# Sheet3.net
KiCad netlist of a schematic drawn in Altium Designer
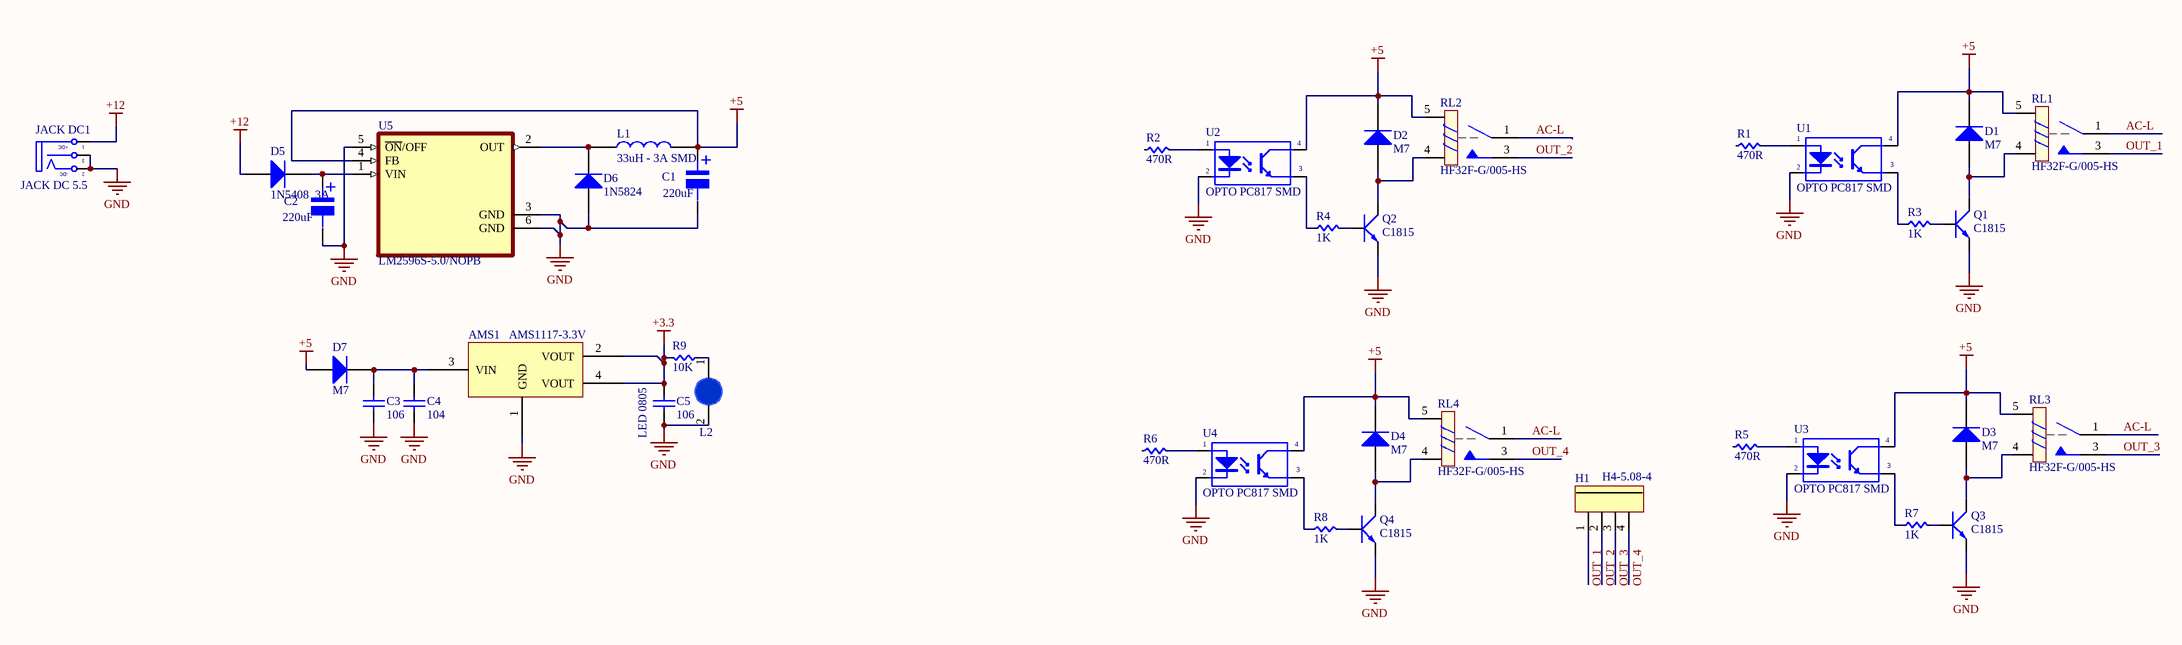
[diagram p0: Sheet3.SchDoc]

(export (version "E")
  (design (tool "Eeschema 10.0.6"))
  (components
    (comp (ref "AMS1")
      (value "AMS1117-3.3V")
      (footprint "SOT223")
      (description "Dán")
      (libsource (lib "Altium_Lib_by_KhueNguyenCreator") (part "AMS1117 SMD"))
    )
    (comp (ref "C1")
      (value "220uF")
      (footprint "tu nhom 10 (G)")
      (description "Dán")
      (libsource (lib "Altium_Lib_by_KhueNguyenCreator") (part "Tu Nhom 470uF 35V"))
    )
    (comp (ref "C2")
      (value "220uF")
      (footprint "tu nhom 10 (G)")
      (description "Dán")
      (libsource (lib "Altium_Lib_by_KhueNguyenCreator") (part "Tu Nhom 470uF 35V"))
    )
    (comp (ref "C3")
      (value "106")
      (footprint "tu 0805")
      (description "Dán")
      (libsource (lib "Altium_Lib_by_KhueNguyenCreator") (part "Tu 0805 106 16V 10%"))
    )
    (comp (ref "C4")
      (value "104")
      (footprint "tu 0805")
      (description "Dán")
      (libsource (lib "Altium_Lib_by_KhueNguyenCreator") (part "Tu 0805 104 50V 10%"))
    )
    (comp (ref "C5")
      (value "106")
      (footprint "tu 0805")
      (description "Dán")
      (libsource (lib "Altium_Lib_by_KhueNguyenCreator") (part "Tu 0805 106 16V 10%"))
    )
    (comp (ref "D1")
      (value "M7")
      (footprint "DIODE SMA")
      (description "Dán")
      (libsource (lib "Altium_Lib_by_KhueNguyenCreator") (part "Diode M7 ( 4007 )"))
    )
    (comp (ref "D2")
      (value "M7")
      (footprint "DIODE SMA")
      (description "Dán")
      (libsource (lib "Altium_Lib_by_KhueNguyenCreator") (part "Diode M7 ( 4007 )"))
    )
    (comp (ref "D3")
      (value "M7")
      (footprint "DIODE SMA")
      (description "Dán")
      (libsource (lib "Altium_Lib_by_KhueNguyenCreator") (part "Diode M7 ( 4007 )"))
    )
    (comp (ref "D4")
      (value "M7")
      (footprint "DIODE SMA")
      (description "Dán")
      (libsource (lib "Altium_Lib_by_KhueNguyenCreator") (part "Diode M7 ( 4007 )"))
    )
    (comp (ref "D5")
      (value "1N5408  3A")
      (footprint "DIODE SMA")
      (description "Dán")
      (libsource (lib "Altium_Lib_by_KhueNguyenCreator") (part "Diode M7 ( 4007 )"))
    )
    (comp (ref "D6")
      (value "1N5824")
      (footprint "DIODE SMA")
      (description "Dán")
      (libsource (lib "Altium_Lib_by_KhueNguyenCreator") (part "Diode SS34 ( 1N5822 )"))
    )
    (comp (ref "D7")
      (value "M7")
      (footprint "DIODE SMA")
      (description "Dán")
      (libsource (lib "Altium_Lib_by_KhueNguyenCreator") (part "Diode M7 ( 4007 )"))
    )
    (comp (ref "H1")
      (value "H4-5.08-4")
      (footprint "KF-5.08-4")
      (libsource (lib "iuh-thuc-hanh") (part "KF-5.08-4-R Cong"))
    )
    (comp (ref "JACK DC1")
      (value "JACK DC 5.5")
      (footprint "JACK DC 5.5")
      (libsource (lib "Altium_Lib_by_KhueNguyenCreator") (part "JACK DC 5.5"))
    )
    (comp (ref "L1")
      (value "33uH - 3A SMD")
      (footprint "Cuon Cam 12x12x10")
      (description "Dán")
      (libsource (lib "Altium_Lib_by_KhueNguyenCreator") (part "CUON CAM 100uH SMD"))
    )
    (comp (ref "L2")
      (value "LED 0805")
      (footprint "LED-0805-Blue")
      (description "Dán")
      (libsource (lib "Altium_Lib_by_KhueNguyenCreator") (part "LED 0805 Xanh Duong"))
    )
    (comp (ref "Q1")
      (value "C1815")
      (footprint "QTO-92")
      (description "NPN 600mW, ECB")
      (libsource (lib "syhaunguyen") (part "C1815"))
    )
    (comp (ref "Q2")
      (value "C1815")
      (footprint "QTO-92")
      (description "NPN 600mW, ECB")
      (libsource (lib "syhaunguyen") (part "C1815"))
    )
    (comp (ref "Q3")
      (value "C1815")
      (footprint "QTO-92")
      (description "NPN 600mW, ECB")
      (libsource (lib "syhaunguyen") (part "C1815"))
    )
    (comp (ref "Q4")
      (value "C1815")
      (footprint "QTO-92")
      (description "NPN 600mW, ECB")
      (libsource (lib "syhaunguyen") (part "C1815"))
    )
    (comp (ref "R1")
      (value "470R")
      (footprint "RES 0805")
      (description "RES SMD 0805")
      (fields
        (field (name "MANUFACTURER") "Vishay Dale")
        (field (name "MANUFACTURER PART NUMBER") "CRCW040210K0FKED")
      )
      (libsource (lib "Altium_Lib_by_KhueNguyenCreator") (part "RES 0805"))
    )
    (comp (ref "R2")
      (value "470R")
      (footprint "RES 0805")
      (description "RES SMD 0805")
      (fields
        (field (name "MANUFACTURER") "Vishay Dale")
        (field (name "MANUFACTURER PART NUMBER") "CRCW040210K0FKED")
      )
      (libsource (lib "Altium_Lib_by_KhueNguyenCreator") (part "RES 0805"))
    )
    (comp (ref "R3")
      (value "1K")
      (footprint "RES 0805")
      (description "RES SMD 0805")
      (fields
        (field (name "MANUFACTURER") "Vishay Dale")
        (field (name "MANUFACTURER PART NUMBER") "CRCW040210K0FKED")
      )
      (libsource (lib "Altium_Lib_by_KhueNguyenCreator") (part "RES 0805"))
    )
    (comp (ref "R4")
      (value "1K")
      (footprint "RES 0805")
      (description "RES SMD 0805")
      (fields
        (field (name "MANUFACTURER") "Vishay Dale")
        (field (name "MANUFACTURER PART NUMBER") "CRCW040210K0FKED")
      )
      (libsource (lib "Altium_Lib_by_KhueNguyenCreator") (part "RES 0805"))
    )
    (comp (ref "R5")
      (value "470R")
      (footprint "RES 0805")
      (description "RES SMD 0805")
      (fields
        (field (name "MANUFACTURER") "Vishay Dale")
        (field (name "MANUFACTURER PART NUMBER") "CRCW040210K0FKED")
      )
      (libsource (lib "Altium_Lib_by_KhueNguyenCreator") (part "RES 0805"))
    )
    (comp (ref "R6")
      (value "470R")
      (footprint "RES 0805")
      (description "RES SMD 0805")
      (fields
        (field (name "MANUFACTURER") "Vishay Dale")
        (field (name "MANUFACTURER PART NUMBER") "CRCW040210K0FKED")
      )
      (libsource (lib "Altium_Lib_by_KhueNguyenCreator") (part "RES 0805"))
    )
    (comp (ref "R7")
      (value "1K")
      (footprint "RES 0805")
      (description "RES SMD 0805")
      (fields
        (field (name "MANUFACTURER") "Vishay Dale")
        (field (name "MANUFACTURER PART NUMBER") "CRCW040210K0FKED")
      )
      (libsource (lib "Altium_Lib_by_KhueNguyenCreator") (part "RES 0805"))
    )
    (comp (ref "R8")
      (value "1K")
      (footprint "RES 0805")
      (description "RES SMD 0805")
      (fields
        (field (name "MANUFACTURER") "Vishay Dale")
        (field (name "MANUFACTURER PART NUMBER") "CRCW040210K0FKED")
      )
      (libsource (lib "Altium_Lib_by_KhueNguyenCreator") (part "RES 0805"))
    )
    (comp (ref "R9")
      (value "10K")
      (footprint "RES 0805")
      (description "RES SMD 0805")
      (fields
        (field (name "MANUFACTURER") "Vishay Dale")
        (field (name "MANUFACTURER PART NUMBER") "CRCW040210K0FKED")
      )
      (libsource (lib "Altium_Lib_by_KhueNguyenCreator") (part "RES 0805"))
    )
    (comp (ref "RL1")
      (value "HF32F-G/005-HS")
      (footprint "HF32F-G")
      (description "Relay hongfa 10A 4P HF32F-G/005-HS")
      (libsource (lib "iuh-thuc-hanh") (part "Relay HF 10A"))
    )
    (comp (ref "RL2")
      (value "HF32F-G/005-HS")
      (footprint "HF32F-G")
      (description "Relay hongfa 10A 4P HF32F-G/005-HS")
      (libsource (lib "iuh-thuc-hanh") (part "Relay HF 10A"))
    )
    (comp (ref "RL3")
      (value "HF32F-G/005-HS")
      (footprint "HF32F-G")
      (description "Relay hongfa 10A 4P HF32F-G/005-HS")
      (libsource (lib "iuh-thuc-hanh") (part "Relay HF 10A"))
    )
    (comp (ref "RL4")
      (value "HF32F-G/005-HS")
      (footprint "HF32F-G")
      (description "Relay hongfa 10A 4P HF32F-G/005-HS")
      (libsource (lib "iuh-thuc-hanh") (part "Relay HF 10A"))
    )
    (comp (ref "U1")
      (value "OPTO PC817 SMD")
      (footprint "SOP4")
      (description "Single Opto")
      (libsource (lib "Altium_Lib_by_KhueNguyenCreator") (part "OPTO PC817 SMD"))
    )
    (comp (ref "U2")
      (value "OPTO PC817 SMD")
      (footprint "SOP4")
      (description "Single Opto")
      (libsource (lib "Altium_Lib_by_KhueNguyenCreator") (part "OPTO PC817 SMD"))
    )
    (comp (ref "U3")
      (value "OPTO PC817 SMD")
      (footprint "SOP4")
      (description "Single Opto")
      (libsource (lib "Altium_Lib_by_KhueNguyenCreator") (part "OPTO PC817 SMD"))
    )
    (comp (ref "U4")
      (value "OPTO PC817 SMD")
      (footprint "SOP4")
      (description "Single Opto")
      (libsource (lib "Altium_Lib_by_KhueNguyenCreator") (part "OPTO PC817 SMD"))
    )
    (comp (ref "U5")
      (value "LM2596S-5.0/NOPB")
      (footprint "VREG_LM2596S-12/NOPB")
      (description "SIMPLE SWITCHERÂ® 4.5V to 40V, 3A Low Component Count Step-Down Regulator")
      (fields (field (name "MF") "Texas Instruments") (field (name "MP") "LM2596S-12/NOPB"))
      (libsource (lib "TuHap") (part "LM2596S-12/NOPB"))
    )
  )
  (nets
    (net (code "1") (name "+3.3") (class "Default")
      (node (ref "AMS1") (pin "2") (pinfunction "VOUT_2") (pintype "passive"))
      (node (ref "AMS1") (pin "4") (pinfunction "VOUT_4") (pintype "passive"))
      (node (ref "C5") (pin "1") (pinfunction "1_1") (pintype "passive"))
      (node (ref "R9") (pin "2") (pinfunction "2_2") (pintype "passive"))
    )
    (net (code "2") (name "+5") (class "Default")
      (node (ref "C1") (pin "1") (pinfunction "1_1") (pintype "passive"))
      (node (ref "D1") (pin "2") (pinfunction "K_2") (pintype "passive"))
      (node (ref "D2") (pin "2") (pinfunction "K_2") (pintype "passive"))
      (node (ref "D3") (pin "2") (pinfunction "K_2") (pintype "passive"))
      (node (ref "D4") (pin "2") (pinfunction "K_2") (pintype "passive"))
      (node (ref "D7") (pin "1") (pinfunction "A_1") (pintype "passive"))
      (node (ref "L1") (pin "2") (pinfunction "2_2") (pintype "passive"))
      (node (ref "RL1") (pin "5") (pinfunction "5_5") (pintype "passive"))
      (node (ref "RL2") (pin "5") (pinfunction "5_5") (pintype "passive"))
      (node (ref "RL3") (pin "5") (pinfunction "5_5") (pintype "passive"))
      (node (ref "RL4") (pin "5") (pinfunction "5_5") (pintype "passive"))
      (node (ref "U1") (pin "4") (pinfunction "C_4") (pintype "passive"))
      (node (ref "U2") (pin "4") (pinfunction "C_4") (pintype "passive"))
      (node (ref "U3") (pin "4") (pinfunction "C_4") (pintype "passive"))
      (node (ref "U4") (pin "4") (pinfunction "C_4") (pintype "passive"))
      (node (ref "U5") (pin "4") (pinfunction "FB_4") (pintype "input"))
    )
    (net (code "3") (name "+12") (class "Default")
      (node (ref "D5") (pin "1") (pinfunction "A_1") (pintype "passive"))
      (node (ref "JACK DC1") (pin "1") (pinfunction "T_1") (pintype "passive"))
    )
    (net (code "4") (name "/AC-L") (class "Default")
      (node (ref "RL1") (pin "1") (pinfunction "1_1") (pintype "passive"))
      (node (ref "RL2") (pin "1") (pinfunction "1_1") (pintype "passive"))
      (node (ref "RL3") (pin "1") (pinfunction "1_1") (pintype "passive"))
      (node (ref "RL4") (pin "1") (pinfunction "1_1") (pintype "passive"))
    )
    (net (code "5") (name "/OUT_1") (class "Default")
      (node (ref "H1") (pin "1") (pinfunction "1_1") (pintype "passive"))
      (node (ref "RL1") (pin "3") (pinfunction "3_3") (pintype "passive"))
    )
    (net (code "6") (name "/OUT_2") (class "Default")
      (node (ref "H1") (pin "2") (pinfunction "2_2") (pintype "passive"))
      (node (ref "RL2") (pin "3") (pinfunction "3_3") (pintype "passive"))
    )
    (net (code "7") (name "/OUT_3") (class "Default")
      (node (ref "H1") (pin "3") (pinfunction "3_3") (pintype "passive"))
      (node (ref "RL3") (pin "3") (pinfunction "3_3") (pintype "passive"))
    )
    (net (code "8") (name "/OUT_4") (class "Default")
      (node (ref "H1") (pin "4") (pinfunction "4_4") (pintype "passive"))
      (node (ref "RL4") (pin "3") (pinfunction "3_3") (pintype "passive"))
    )
    (net (code "9") (name "GND") (class "Default")
      (node (ref "AMS1") (pin "1") (pinfunction "GND_1") (pintype "passive"))
      (node (ref "C1") (pin "2") (pinfunction "2_2") (pintype "passive"))
      (node (ref "C2") (pin "2") (pinfunction "2_2") (pintype "passive"))
      (node (ref "C3") (pin "2") (pinfunction "2_2") (pintype "passive"))
      (node (ref "C4") (pin "2") (pinfunction "2_2") (pintype "passive"))
      (node (ref "C5") (pin "2") (pinfunction "2_2") (pintype "passive"))
      (node (ref "D6") (pin "1") (pinfunction "A_1") (pintype "passive"))
      (node (ref "JACK DC1") (pin "2") (pinfunction "TN_2") (pintype "passive"))
      (node (ref "JACK DC1") (pin "3") (pinfunction "S_3") (pintype "power_in"))
      (node (ref "L2") (pin "2") (pinfunction "K_2") (pintype "passive"))
      (node (ref "Q1") (pin "1") (pinfunction "E_1") (pintype "passive"))
      (node (ref "Q2") (pin "1") (pinfunction "E_1") (pintype "passive"))
      (node (ref "Q3") (pin "1") (pinfunction "E_1") (pintype "passive"))
      (node (ref "Q4") (pin "1") (pinfunction "E_1") (pintype "passive"))
      (node (ref "U1") (pin "2") (pinfunction "K_2") (pintype "passive"))
      (node (ref "U2") (pin "2") (pinfunction "K_2") (pintype "passive"))
      (node (ref "U3") (pin "2") (pinfunction "K_2") (pintype "passive"))
      (node (ref "U4") (pin "2") (pinfunction "K_2") (pintype "passive"))
      (node (ref "U5") (pin "3") (pinfunction "GND_3") (pintype "power_in"))
      (node (ref "U5") (pin "5") (pinfunction "~{ON}/OFF_5") (pintype "input"))
      (node (ref "U5") (pin "6") (pinfunction "GND_6") (pintype "power_in"))
    )
    (net (code "10") (name "Net-(AMS1-VIN)") (class "Default")
      (node (ref "AMS1") (pin "3") (pinfunction "VIN_3") (pintype "passive"))
      (node (ref "C3") (pin "1") (pinfunction "1_1") (pintype "passive"))
      (node (ref "C4") (pin "1") (pinfunction "1_1") (pintype "passive"))
      (node (ref "D7") (pin "2") (pinfunction "K_2") (pintype "passive"))
    )
    (net (code "11") (name "Net-(D1-A)") (class "Default")
      (node (ref "D1") (pin "1") (pinfunction "A_1") (pintype "passive"))
      (node (ref "Q1") (pin "2") (pinfunction "C_2") (pintype "passive"))
      (node (ref "RL1") (pin "4") (pinfunction "4_4") (pintype "passive"))
    )
    (net (code "12") (name "Net-(D2-A)") (class "Default")
      (node (ref "D2") (pin "1") (pinfunction "A_1") (pintype "passive"))
      (node (ref "Q2") (pin "2") (pinfunction "C_2") (pintype "passive"))
      (node (ref "RL2") (pin "4") (pinfunction "4_4") (pintype "passive"))
    )
    (net (code "13") (name "Net-(D3-A)") (class "Default")
      (node (ref "D3") (pin "1") (pinfunction "A_1") (pintype "passive"))
      (node (ref "Q3") (pin "2") (pinfunction "C_2") (pintype "passive"))
      (node (ref "RL3") (pin "4") (pinfunction "4_4") (pintype "passive"))
    )
    (net (code "14") (name "Net-(D4-A)") (class "Default")
      (node (ref "D4") (pin "1") (pinfunction "A_1") (pintype "passive"))
      (node (ref "Q4") (pin "2") (pinfunction "C_2") (pintype "passive"))
      (node (ref "RL4") (pin "4") (pinfunction "4_4") (pintype "passive"))
    )
    (net (code "15") (name "Net-(D5-K)") (class "Default")
      (node (ref "C2") (pin "1") (pinfunction "1_1") (pintype "passive"))
      (node (ref "D5") (pin "2") (pinfunction "K_2") (pintype "passive"))
      (node (ref "U5") (pin "1") (pinfunction "VIN_1") (pintype "input"))
    )
    (net (code "16") (name "Net-(D6-K)") (class "Default")
      (node (ref "D6") (pin "2") (pinfunction "K_2") (pintype "passive"))
      (node (ref "L1") (pin "1") (pinfunction "1_1") (pintype "passive"))
      (node (ref "U5") (pin "2") (pinfunction "OUT_2") (pintype "output"))
    )
    (net (code "17") (name "Net-(L2-A)") (class "Default")
      (node (ref "L2") (pin "1") (pinfunction "A_1") (pintype "passive"))
      (node (ref "R9") (pin "1") (pinfunction "1_1") (pintype "passive"))
    )
    (net (code "18") (name "Net-(Q1-B)") (class "Default")
      (node (ref "Q1") (pin "3") (pinfunction "B_3") (pintype "passive"))
      (node (ref "R3") (pin "2") (pinfunction "2_2") (pintype "passive"))
    )
    (net (code "19") (name "Net-(Q2-B)") (class "Default")
      (node (ref "Q2") (pin "3") (pinfunction "B_3") (pintype "passive"))
      (node (ref "R4") (pin "2") (pinfunction "2_2") (pintype "passive"))
    )
    (net (code "20") (name "Net-(Q3-B)") (class "Default")
      (node (ref "Q3") (pin "3") (pinfunction "B_3") (pintype "passive"))
      (node (ref "R7") (pin "2") (pinfunction "2_2") (pintype "passive"))
    )
    (net (code "21") (name "Net-(Q4-B)") (class "Default")
      (node (ref "Q4") (pin "3") (pinfunction "B_3") (pintype "passive"))
      (node (ref "R8") (pin "2") (pinfunction "2_2") (pintype "passive"))
    )
    (net (code "22") (name "Net-(U1-A)") (class "Default")
      (node (ref "R1") (pin "2") (pinfunction "2_2") (pintype "passive"))
      (node (ref "U1") (pin "1") (pinfunction "A_1") (pintype "passive"))
    )
    (net (code "23") (name "Net-(U1-E)") (class "Default")
      (node (ref "R3") (pin "1") (pinfunction "1_1") (pintype "passive"))
      (node (ref "U1") (pin "3") (pinfunction "E_3") (pintype "passive"))
    )
    (net (code "24") (name "Net-(U2-A)") (class "Default")
      (node (ref "R2") (pin "2") (pinfunction "2_2") (pintype "passive"))
      (node (ref "U2") (pin "1") (pinfunction "A_1") (pintype "passive"))
    )
    (net (code "25") (name "Net-(U2-E)") (class "Default")
      (node (ref "R4") (pin "1") (pinfunction "1_1") (pintype "passive"))
      (node (ref "U2") (pin "3") (pinfunction "E_3") (pintype "passive"))
    )
    (net (code "26") (name "Net-(U3-A)") (class "Default")
      (node (ref "R5") (pin "2") (pinfunction "2_2") (pintype "passive"))
      (node (ref "U3") (pin "1") (pinfunction "A_1") (pintype "passive"))
    )
    (net (code "27") (name "Net-(U3-E)") (class "Default")
      (node (ref "R7") (pin "1") (pinfunction "1_1") (pintype "passive"))
      (node (ref "U3") (pin "3") (pinfunction "E_3") (pintype "passive"))
    )
    (net (code "28") (name "Net-(U4-A)") (class "Default")
      (node (ref "R6") (pin "2") (pinfunction "2_2") (pintype "passive"))
      (node (ref "U4") (pin "1") (pinfunction "A_1") (pintype "passive"))
    )
    (net (code "29") (name "Net-(U4-E)") (class "Default")
      (node (ref "R8") (pin "1") (pinfunction "1_1") (pintype "passive"))
      (node (ref "U4") (pin "3") (pinfunction "E_3") (pintype "passive"))
    )
    (net (code "30") (name "unconnected-(R1-Pad1)") (class "Default")
      (node (ref "R1") (pin "1") (pinfunction "1_1") (pintype "passive"))
    )
    (net (code "31") (name "unconnected-(R2-Pad1)") (class "Default")
      (node (ref "R2") (pin "1") (pinfunction "1_1") (pintype "passive"))
    )
    (net (code "32") (name "unconnected-(R5-Pad1)") (class "Default")
      (node (ref "R5") (pin "1") (pinfunction "1_1") (pintype "passive"))
    )
    (net (code "33") (name "unconnected-(R6-Pad1)") (class "Default")
      (node (ref "R6") (pin "1") (pinfunction "1_1") (pintype "passive"))
    )
  )
)
